# noise_generator.net
KiCad netlist of a schematic drawn in EAGLE
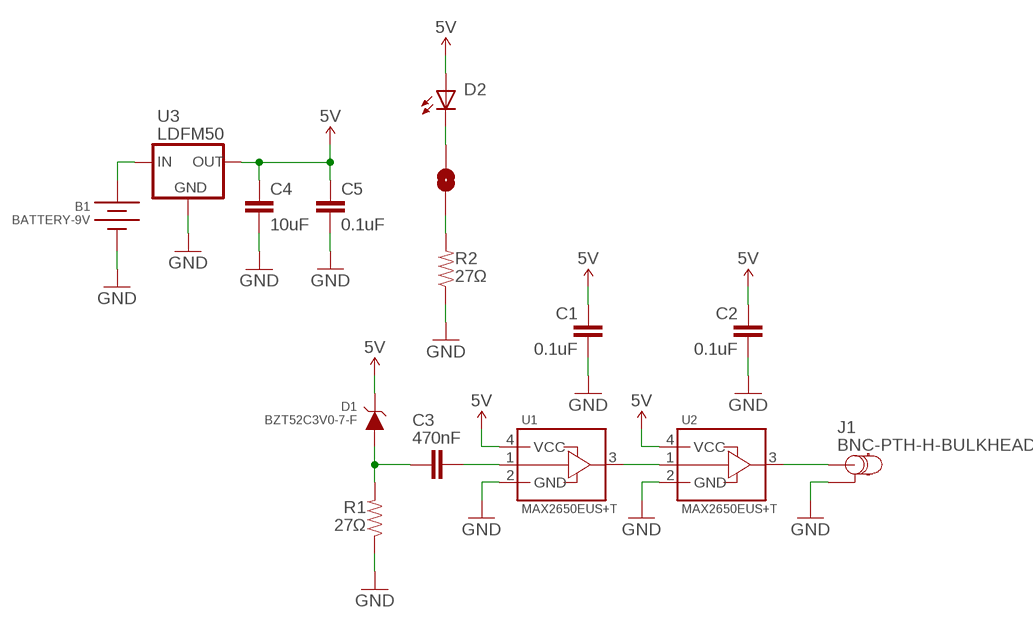
[diagram p0: schematic, sheet 1]

(export (version "E")
  (design (tool "Eeschema 10.0.6"))
  (components
    (comp (ref "B1")
      (value "BATTERY-9V")
      (footprint "eagle-import:9V-NEG")
      (libsource (lib "eagle-import") (part "BATTERY-9V"))
    )
    (comp (ref "C1")
      (value "0.1uF")
      (footprint "eagle-import:1206")
      (libsource (lib "eagle-import") (part "CAP-1206"))
    )
    (comp (ref "C2")
      (value "0.1uF")
      (footprint "eagle-import:1206")
      (libsource (lib "eagle-import") (part "CAP-1206"))
    )
    (comp (ref "C3")
      (value "470nF")
      (footprint "eagle-import:1206")
      (libsource (lib "eagle-import") (part "CAP-1206"))
    )
    (comp (ref "C4")
      (value "10uF")
      (footprint "eagle-import:1206")
      (libsource (lib "eagle-import") (part "CAP-1206"))
    )
    (comp (ref "C5")
      (value "0.1uF")
      (footprint "eagle-import:1206")
      (libsource (lib "eagle-import") (part "CAP-1206"))
    )
    (comp (ref "D1")
      (value "BZT52C3V0-7-F")
      (footprint "eagle-import:SOD123")
      (libsource (lib "eagle-import") (part "BZT52C3V0-7-F"))
    )
    (comp (ref "D2")
      (value "LED-0805")
      (footprint "eagle-import:0805-LED")
      (libsource (lib "eagle-import") (part "LED-0805"))
    )
    (comp (ref "J1")
      (value "BNC-PTH-H-BULKHEAD")
      (footprint "eagle-import:BNC-5-1634556-0")
      (libsource (lib "eagle-import") (part "BNC-PTH-H-BULKHEAD"))
    )
    (comp (ref "R1")
      (value "27Ω")
      (footprint "eagle-import:1206")
      (libsource (lib "eagle-import") (part "RESISTOR-1206"))
    )
    (comp (ref "R2")
      (value "27Ω")
      (footprint "eagle-import:1206")
      (libsource (lib "eagle-import") (part "RESISTOR-1206"))
    )
    (comp (ref "SJ1")
      (value "SOLDERJUMPERNO")
      (footprint "eagle-import:SJ_2S-NO")
      (libsource (lib "eagle-import") (part "SOLDERJUMPERNO"))
    )
    (comp (ref "U1")
      (value "MAX2650EUS+T")
      (footprint "eagle-import:SOT-143-4")
      (libsource (lib "eagle-import") (part "MAX2650EUS+T"))
    )
    (comp (ref "U2")
      (value "MAX2650EUS+T")
      (footprint "eagle-import:SOT-143-4")
      (libsource (lib "eagle-import") (part "MAX2650EUS+T"))
    )
    (comp (ref "U3")
      (value "LDFM50")
      (footprint "eagle-import:DPAK")
      (libsource (lib "eagle-import") (part "LDFM50"))
    )
  )
  (nets
    (net (code "1") (name "5V") (class "Default")
      (node (ref "C1") (pin "1") (pinfunction "1_1") (pintype "passive"))
      (node (ref "C2") (pin "1") (pinfunction "1_1") (pintype "passive"))
      (node (ref "C4") (pin "1") (pinfunction "1_1") (pintype "passive"))
      (node (ref "C5") (pin "1") (pinfunction "1_1") (pintype "passive"))
      (node (ref "D1") (pin "CATHODE") (pinfunction "C_CATHODE") (pintype "bidirectional"))
      (node (ref "D2") (pin "A") (pinfunction "A_A") (pintype "passive"))
      (node (ref "U1") (pin "4") (pinfunction "VCC_4") (pintype "bidirectional"))
      (node (ref "U2") (pin "4") (pinfunction "VCC_4") (pintype "bidirectional"))
      (node (ref "U3") (pin "3") (pinfunction "OUT_3") (pintype "output"))
    )
    (net (code "2") (name "GND") (class "Default")
      (node (ref "B1") (pin "N1") (pinfunction "N_N1") (pintype "bidirectional"))
      (node (ref "B1") (pin "N2") (pinfunction "N_N2") (pintype "bidirectional"))
      (node (ref "B1") (pin "N3") (pinfunction "N_N3") (pintype "bidirectional"))
      (node (ref "C1") (pin "2") (pinfunction "2_2") (pintype "passive"))
      (node (ref "C2") (pin "2") (pinfunction "2_2") (pintype "passive"))
      (node (ref "C4") (pin "2") (pinfunction "2_2") (pintype "passive"))
      (node (ref "C5") (pin "2") (pinfunction "2_2") (pintype "passive"))
      (node (ref "J1") (pin "P$1") (pinfunction "GND_P$1") (pintype "bidirectional"))
      (node (ref "J1") (pin "P$2") (pinfunction "GND_P$2") (pintype "bidirectional"))
      (node (ref "J1") (pin "P$3") (pinfunction "GND_P$3") (pintype "bidirectional"))
      (node (ref "J1") (pin "P$4") (pinfunction "GND_P$4") (pintype "bidirectional"))
      (node (ref "R1") (pin "1") (pinfunction "1_1") (pintype "passive"))
      (node (ref "R2") (pin "1") (pinfunction "1_1") (pintype "passive"))
      (node (ref "U1") (pin "2") (pinfunction "GND_2") (pintype "bidirectional"))
      (node (ref "U2") (pin "2") (pinfunction "GND_2") (pintype "bidirectional"))
      (node (ref "U3") (pin "TAB") (pinfunction "GND_TAB") (pintype "input"))
    )
    (net (code "3") (name "Net-(D1-A)") (class "Default")
      (node (ref "C3") (pin "1") (pinfunction "1_1") (pintype "passive"))
      (node (ref "D1") (pin "ANODE") (pinfunction "A_ANODE") (pintype "bidirectional"))
      (node (ref "R1") (pin "2") (pinfunction "2_2") (pintype "passive"))
    )
    (net (code "4") (name "Net-(D2-PadC)") (class "Default")
      (node (ref "D2") (pin "C") (pinfunction "C_C") (pintype "passive"))
      (node (ref "SJ1") (pin "2") (pinfunction "2_2") (pintype "passive"))
    )
    (net (code "5") (name "Net-(J1-SIGNAL)") (class "Default")
      (node (ref "J1") (pin "1") (pinfunction "SIGNAL_1") (pintype "bidirectional"))
      (node (ref "U2") (pin "3") (pinfunction "OUT_3") (pintype "bidirectional"))
    )
    (net (code "6") (name "Net-(R2-Pad2)") (class "Default")
      (node (ref "R2") (pin "2") (pinfunction "2_2") (pintype "passive"))
      (node (ref "SJ1") (pin "1") (pinfunction "1_1") (pintype "passive"))
    )
    (net (code "7") (name "Net-(U1-IN)") (class "Default")
      (node (ref "C3") (pin "2") (pinfunction "2_2") (pintype "passive"))
      (node (ref "U1") (pin "1") (pinfunction "IN_1") (pintype "bidirectional"))
    )
    (net (code "8") (name "Net-(U1-OUT)") (class "Default")
      (node (ref "U1") (pin "3") (pinfunction "OUT_3") (pintype "bidirectional"))
      (node (ref "U2") (pin "1") (pinfunction "IN_1") (pintype "bidirectional"))
    )
    (net (code "9") (name "Net-(U3-IN)") (class "Default")
      (node (ref "B1") (pin "P1") (pinfunction "P_P1") (pintype "bidirectional"))
      (node (ref "B1") (pin "P2") (pinfunction "P_P2") (pintype "bidirectional"))
      (node (ref "B1") (pin "P3") (pinfunction "P_P3") (pintype "bidirectional"))
      (node (ref "U3") (pin "1") (pinfunction "IN_1") (pintype "input"))
    )
  )
)
